# Tracksoar_v1_2.net
KiCad netlist of a schematic drawn in EAGLE
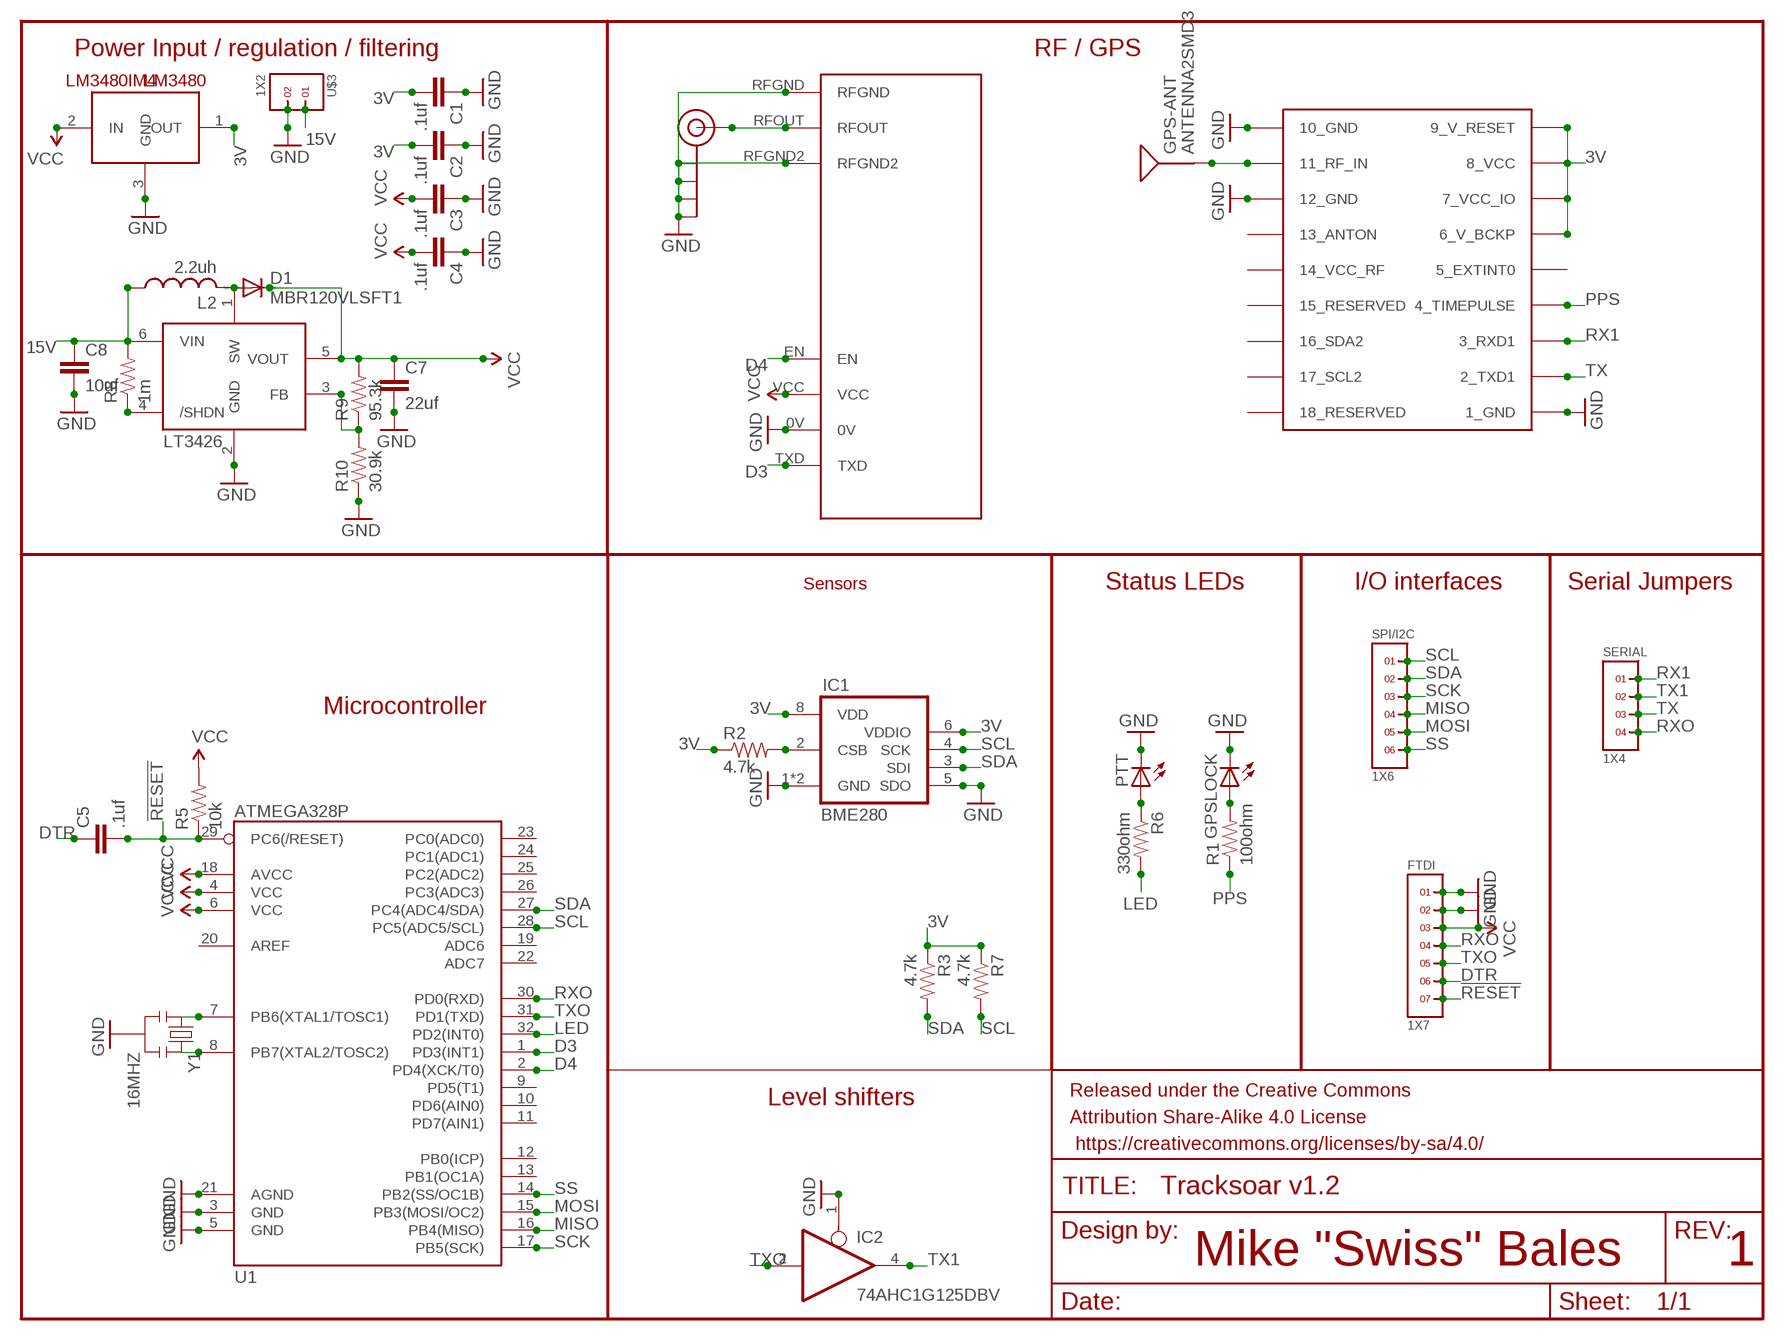
[diagram p0: schematic, sheet 1]

(export (version "E")
  (design (tool "Eeschema 10.0.6"))
  (components
    (comp (ref "C1")
      (value ".1uf")
      (footprint "eagle-import:0805")
      (libsource (lib "eagle-import") (part "CAP0805"))
    )
    (comp (ref "C2")
      (value ".1uf")
      (footprint "eagle-import:0805")
      (libsource (lib "eagle-import") (part "CAP0805"))
    )
    (comp (ref "C3")
      (value ".1uf")
      (footprint "eagle-import:0805")
      (libsource (lib "eagle-import") (part "CAP0805"))
    )
    (comp (ref "C4")
      (value ".1uf")
      (footprint "eagle-import:0805")
      (libsource (lib "eagle-import") (part "CAP0805"))
    )
    (comp (ref "C5")
      (value ".1uf")
      (footprint "eagle-import:0805")
      (libsource (lib "eagle-import") (part "CAP0805"))
    )
    (comp (ref "C7")
      (value "22uf")
      (footprint "eagle-import:0805")
      (libsource (lib "eagle-import") (part "CAP0805"))
    )
    (comp (ref "C8")
      (value "10uf")
      (footprint "eagle-import:0805")
      (libsource (lib "eagle-import") (part "CAP0805"))
    )
    (comp (ref "D1")
      (value "MBR120VLSFT1")
      (footprint "eagle-import:SOD123")
      (libsource (lib "eagle-import") (part "DIODE-SOD123"))
    )
    (comp (ref "FRAME1")
      (value "FRAME-LETTER")
      (footprint "eagle-import:CREATIVE_COMMONS")
      (libsource (lib "eagle-import") (part "FRAME-LETTER"))
    )
    (comp (ref "FTDI")
      (value "1X7")
      (footprint "eagle-import:1X7")
      (libsource (lib "eagle-import") (part "1X7"))
    )
    (comp (ref "GPS-ANT")
      (value "ANTENNA2SMD3")
      (footprint "eagle-import:ANTENNA-CHIP4")
      (libsource (lib "eagle-import") (part "ANTENNA2SMD3"))
    )
    (comp (ref "GPSLOCK")
      (value "LEDCHIP-LED0805")
      (footprint "eagle-import:CHIP-LED0805")
      (libsource (lib "eagle-import") (part "LEDCHIP-LED0805"))
    )
    (comp (ref "IC1")
      (value "BME280")
      (footprint "eagle-import:BME280")
      (libsource (lib "eagle-import") (part "BME280"))
    )
    (comp (ref "IC2")
      (value "74AHC1G125DBV")
      (footprint "eagle-import:SOT23-5")
      (libsource (lib "eagle-import") (part "741G125DBVAHC"))
    )
    (comp (ref "J$1")
      (value "SMA_EDGE")
      (footprint "eagle-import:SMA-EDGE")
      (libsource (lib "eagle-import") (part "SMA_EDGE"))
    )
    (comp (ref "L2")
      (value "2.2uh")
      (footprint "eagle-import:L1812")
      (libsource (lib "eagle-import") (part "L-USL1812"))
    )
    (comp (ref "LM3480")
      (value "LM3480IM4")
      (footprint "eagle-import:SOT23-3")
      (libsource (lib "eagle-import") (part "LM3480IM4"))
    )
    (comp (ref "LT3426")
      (value "LT3426")
      (footprint "eagle-import:SOT23-6")
      (libsource (lib "eagle-import") (part "LT3426"))
    )
    (comp (ref "PTT")
      (value "LEDCHIP-LED0805")
      (footprint "eagle-import:CHIP-LED0805")
      (libsource (lib "eagle-import") (part "LEDCHIP-LED0805"))
    )
    (comp (ref "R1")
      (value "100ohm")
      (footprint "eagle-import:0805")
      (libsource (lib "eagle-import") (part "RESISTOR0805-RES"))
    )
    (comp (ref "R2")
      (value "4.7k")
      (footprint "eagle-import:0805")
      (libsource (lib "eagle-import") (part "RESISTOR0805-RES"))
    )
    (comp (ref "R3")
      (value "4.7k")
      (footprint "eagle-import:0805")
      (libsource (lib "eagle-import") (part "RESISTOR0805-RES"))
    )
    (comp (ref "R5")
      (value "10k")
      (footprint "eagle-import:0805")
      (libsource (lib "eagle-import") (part "RESISTOR0805-RES"))
    )
    (comp (ref "R6")
      (value "330ohm")
      (footprint "eagle-import:0805")
      (libsource (lib "eagle-import") (part "RESISTOR0805-RES"))
    )
    (comp (ref "R7")
      (value "4.7k")
      (footprint "eagle-import:0805")
      (libsource (lib "eagle-import") (part "RESISTOR0805-RES"))
    )
    (comp (ref "R8")
      (value "1m")
      (footprint "eagle-import:0805")
      (libsource (lib "eagle-import") (part "RESISTOR0805-RES"))
    )
    (comp (ref "R9")
      (value "95.3k")
      (footprint "eagle-import:0805")
      (libsource (lib "eagle-import") (part "RESISTOR0805-RES"))
    )
    (comp (ref "R10")
      (value "30.9k")
      (footprint "eagle-import:0805")
      (libsource (lib "eagle-import") (part "RESISTOR0805-RES"))
    )
    (comp (ref "SERIAL")
      (value "1X4")
      (footprint "eagle-import:1X4")
      (libsource (lib "eagle-import") (part "1X4"))
    )
    (comp (ref "SPI/I2C")
      (value "1X6")
      (footprint "eagle-import:1X6")
      (libsource (lib "eagle-import") (part "1X6"))
    )
    (comp (ref "U$1")
      (value "UBLOX_MAX")
      (footprint "eagle-import:UBLOX_MAX")
      (libsource (lib "eagle-import") (part "UBLOX_MAX"))
    )
    (comp (ref "U$2")
      (value "RADIOMETRIX-HX1")
      (footprint "eagle-import:RADIOMETRIX-HX1")
      (libsource (lib "eagle-import") (part "RADIOMETRIX-HX1"))
    )
    (comp (ref "U$3")
      (value "1X2")
      (footprint "eagle-import:1X2")
      (libsource (lib "eagle-import") (part "1X2"))
    )
    (comp (ref "U1")
      (value "ATMEGA328P")
      (footprint "eagle-import:MLF32")
      (libsource (lib "eagle-import") (part "ATMEGA168MLF"))
    )
    (comp (ref "Y1")
      (value "16MHZ")
      (footprint "eagle-import:RESONATOR-SMD")
      (libsource (lib "eagle-import") (part "RESONATOR16MHZ"))
    )
  )
  (nets
    (net (code "1") (name "/3V") (class "Default")
      (node (ref "C1") (pin "2") (pinfunction "2_2") (pintype "passive"))
      (node (ref "C2") (pin "2") (pinfunction "2_2") (pintype "passive"))
      (node (ref "IC1") (pin "6") (pinfunction "VDDIO_6") (pintype "power_in"))
      (node (ref "IC1") (pin "8") (pinfunction "VDD_8") (pintype "power_in"))
      (node (ref "LM3480") (pin "1") (pinfunction "OUT_1") (pintype "bidirectional"))
      (node (ref "R2") (pin "1") (pinfunction "1_1") (pintype "passive"))
      (node (ref "R3") (pin "1") (pinfunction "1_1") (pintype "passive"))
      (node (ref "R7") (pin "1") (pinfunction "1_1") (pintype "passive"))
      (node (ref "U$1") (pin "6_V_BCKP") (pinfunction "6_V_BCKP_6_V_BCKP") (pintype "bidirectional"))
      (node (ref "U$1") (pin "7_VCC_IO") (pinfunction "7_VCC_IO_7_VCC_IO") (pintype "power_in"))
      (node (ref "U$1") (pin "8_VCC") (pinfunction "8_VCC_8_VCC") (pintype "power_in"))
      (node (ref "U$1") (pin "9_V_RESET") (pinfunction "9_V_RESET_9_V_RESET") (pintype "power_in"))
    )
    (net (code "2") (name "/15V") (class "Default")
      (node (ref "C8") (pin "1") (pinfunction "1_1") (pintype "passive"))
      (node (ref "L2") (pin "1") (pinfunction "1_1") (pintype "passive"))
      (node (ref "LT3426") (pin "6") (pinfunction "VIN_6") (pintype "input"))
      (node (ref "R8") (pin "2") (pinfunction "2_2") (pintype "passive"))
      (node (ref "U$3") (pin "1") (pinfunction "1_1") (pintype "bidirectional"))
    )
    (net (code "3") (name "/D3") (class "Default")
      (node (ref "U$2") (pin "TXD") (pinfunction "TXD_TXD") (pintype "bidirectional"))
      (node (ref "U1") (pin "1") (pinfunction "PD3(INT1)_1") (pintype "bidirectional"))
    )
    (net (code "4") (name "/D4") (class "Default")
      (node (ref "U$2") (pin "EN") (pinfunction "EN_EN") (pintype "bidirectional"))
      (node (ref "U1") (pin "2") (pinfunction "PD4(XCK/T0)_2") (pintype "bidirectional"))
    )
    (net (code "5") (name "/DTR") (class "Default")
      (node (ref "C5") (pin "1") (pinfunction "1_1") (pintype "passive"))
      (node (ref "FTDI") (pin "6") (pinfunction "6_6") (pintype "bidirectional"))
    )
    (net (code "6") (name "/LED") (class "Default")
      (node (ref "R6") (pin "2") (pinfunction "2_2") (pintype "passive"))
      (node (ref "U1") (pin "32") (pinfunction "PD2(INT0)_32") (pintype "bidirectional"))
    )
    (net (code "7") (name "/MISO") (class "Default")
      (node (ref "SPI/I2C") (pin "4") (pinfunction "4_4") (pintype "bidirectional"))
      (node (ref "U1") (pin "16") (pinfunction "PB4(MISO)_16") (pintype "bidirectional"))
    )
    (net (code "8") (name "/MOSI") (class "Default")
      (node (ref "SPI/I2C") (pin "5") (pinfunction "5_5") (pintype "bidirectional"))
      (node (ref "U1") (pin "15") (pinfunction "PB3(MOSI/OC2)_15") (pintype "bidirectional"))
    )
    (net (code "9") (name "/PPS") (class "Default")
      (node (ref "R1") (pin "1") (pinfunction "1_1") (pintype "passive"))
      (node (ref "U$1") (pin "4_TIMEPULSE") (pinfunction "4_TIMEPULSE_4_TIMEPULSE") (pintype "bidirectional"))
    )
    (net (code "10") (name "/RX1") (class "Default")
      (node (ref "SERIAL") (pin "1") (pinfunction "1_1") (pintype "bidirectional"))
      (node (ref "U$1") (pin "3_RXD1") (pinfunction "3_RXD1_3_RXD1") (pintype "bidirectional"))
    )
    (net (code "11") (name "/RXO") (class "Default")
      (node (ref "FTDI") (pin "4") (pinfunction "4_4") (pintype "bidirectional"))
      (node (ref "SERIAL") (pin "4") (pinfunction "4_4") (pintype "bidirectional"))
      (node (ref "U1") (pin "30") (pinfunction "PD0(RXD)_30") (pintype "bidirectional"))
    )
    (net (code "12") (name "/SCK") (class "Default")
      (node (ref "SPI/I2C") (pin "3") (pinfunction "3_3") (pintype "bidirectional"))
      (node (ref "U1") (pin "17") (pinfunction "PB5(SCK)_17") (pintype "bidirectional"))
    )
    (net (code "13") (name "/SCL") (class "Default")
      (node (ref "IC1") (pin "4") (pinfunction "SCK_4") (pintype "bidirectional"))
      (node (ref "R7") (pin "2") (pinfunction "2_2") (pintype "passive"))
      (node (ref "SPI/I2C") (pin "1") (pinfunction "1_1") (pintype "bidirectional"))
      (node (ref "U1") (pin "28") (pinfunction "PC5(ADC5/SCL)_28") (pintype "bidirectional"))
    )
    (net (code "14") (name "/SDA") (class "Default")
      (node (ref "IC1") (pin "3") (pinfunction "SDI_3") (pintype "bidirectional"))
      (node (ref "R3") (pin "2") (pinfunction "2_2") (pintype "passive"))
      (node (ref "SPI/I2C") (pin "2") (pinfunction "2_2") (pintype "bidirectional"))
      (node (ref "U1") (pin "27") (pinfunction "PC4(ADC4/SDA)_27") (pintype "bidirectional"))
    )
    (net (code "15") (name "/SS") (class "Default")
      (node (ref "SPI/I2C") (pin "6") (pinfunction "6_6") (pintype "bidirectional"))
      (node (ref "U1") (pin "14") (pinfunction "PB2(SS/OC1B)_14") (pintype "bidirectional"))
    )
    (net (code "16") (name "/TX") (class "Default")
      (node (ref "SERIAL") (pin "3") (pinfunction "3_3") (pintype "bidirectional"))
      (node (ref "U$1") (pin "2_TXD1") (pinfunction "2_TXD1_2_TXD1") (pintype "bidirectional"))
    )
    (net (code "17") (name "/TX1") (class "Default")
      (node (ref "IC2") (pin "4") (pinfunction "O_4") (pintype "tri_state"))
      (node (ref "SERIAL") (pin "2") (pinfunction "2_2") (pintype "bidirectional"))
    )
    (net (code "18") (name "/TXO") (class "Default")
      (node (ref "FTDI") (pin "5") (pinfunction "5_5") (pintype "bidirectional"))
      (node (ref "IC2") (pin "2") (pinfunction "I_2") (pintype "input"))
      (node (ref "U1") (pin "31") (pinfunction "PD1(TXD)_31") (pintype "bidirectional"))
    )
    (net (code "19") (name "/~{RESET}") (class "Default")
      (node (ref "C5") (pin "2") (pinfunction "2_2") (pintype "passive"))
      (node (ref "FTDI") (pin "7") (pinfunction "7_7") (pintype "bidirectional"))
      (node (ref "R5") (pin "1") (pinfunction "1_1") (pintype "passive"))
      (node (ref "U1") (pin "29") (pinfunction "PC6(/RESET)_29") (pintype "bidirectional"))
    )
    (net (code "20") (name "GND") (class "Default")
      (node (ref "C1") (pin "1") (pinfunction "1_1") (pintype "passive"))
      (node (ref "C2") (pin "1") (pinfunction "1_1") (pintype "passive"))
      (node (ref "C3") (pin "1") (pinfunction "1_1") (pintype "passive"))
      (node (ref "C4") (pin "1") (pinfunction "1_1") (pintype "passive"))
      (node (ref "C7") (pin "2") (pinfunction "2_2") (pintype "passive"))
      (node (ref "C8") (pin "2") (pinfunction "2_2") (pintype "passive"))
      (node (ref "FTDI") (pin "1") (pinfunction "1_1") (pintype "bidirectional"))
      (node (ref "FTDI") (pin "2") (pinfunction "2_2") (pintype "bidirectional"))
      (node (ref "GPSLOCK") (pin "C") (pinfunction "C_C") (pintype "passive"))
      (node (ref "IC1") (pin "1") (pinfunction "GND_1") (pintype "power_in"))
      (node (ref "IC1") (pin "5") (pinfunction "SDO_5") (pintype "input"))
      (node (ref "IC1") (pin "7") (pinfunction "GND_7") (pintype "power_in"))
      (node (ref "IC2") (pin "1") (pinfunction "OE_1") (pintype "input"))
      (node (ref "J$1") (pin "GND@0") (pinfunction "GND_GND@0") (pintype "bidirectional"))
      (node (ref "J$1") (pin "GND@1") (pinfunction "GND_GND@1") (pintype "bidirectional"))
      (node (ref "J$1") (pin "GND@2") (pinfunction "GND_GND@2") (pintype "bidirectional"))
      (node (ref "J$1") (pin "GND@3") (pinfunction "GND_GND@3") (pintype "bidirectional"))
      (node (ref "LM3480") (pin "3") (pinfunction "GND_3") (pintype "bidirectional"))
      (node (ref "LT3426") (pin "2") (pinfunction "GND_2") (pintype "power_in"))
      (node (ref "PTT") (pin "C") (pinfunction "C_C") (pintype "passive"))
      (node (ref "R10") (pin "1") (pinfunction "1_1") (pintype "passive"))
      (node (ref "U$1") (pin "10_GND") (pinfunction "10_GND_10_GND") (pintype "power_in"))
      (node (ref "U$1") (pin "12_GND") (pinfunction "12_GND_12_GND") (pintype "power_in"))
      (node (ref "U$1") (pin "1_GND") (pinfunction "1_GND_1_GND") (pintype "power_in"))
      (node (ref "U$2") (pin "0V") (pinfunction "0V_0V") (pintype "bidirectional"))
      (node (ref "U$2") (pin "RFGND") (pinfunction "RFGND_RFGND") (pintype "bidirectional"))
      (node (ref "U$2") (pin "RFGND2") (pinfunction "RFGND2_RFGND2") (pintype "bidirectional"))
      (node (ref "U$3") (pin "2") (pinfunction "2_2") (pintype "bidirectional"))
      (node (ref "U1") (pin "21") (pinfunction "AGND_21") (pintype "bidirectional"))
      (node (ref "U1") (pin "3") (pinfunction "GND_3") (pintype "bidirectional"))
      (node (ref "U1") (pin "5") (pinfunction "GND_5") (pintype "bidirectional"))
      (node (ref "Y1") (pin "2") (pinfunction "2_2") (pintype "passive"))
    )
    (net (code "21") (name "Net-(GPS-ANT-SIGNAL)") (class "Default")
      (node (ref "GPS-ANT") (pin "SIG") (pinfunction "SIGNAL_SIG") (pintype "bidirectional"))
      (node (ref "U$1") (pin "11_RF_IN") (pinfunction "11_RF_IN_11_RF_IN") (pintype "bidirectional"))
    )
    (net (code "22") (name "Net-(GPSLOCK-PadA)") (class "Default")
      (node (ref "GPSLOCK") (pin "A") (pinfunction "A_A") (pintype "passive"))
      (node (ref "R1") (pin "2") (pinfunction "2_2") (pintype "passive"))
    )
    (net (code "23") (name "Net-(IC1-CSB)") (class "Default")
      (node (ref "IC1") (pin "2") (pinfunction "CSB_2") (pintype "input"))
      (node (ref "R2") (pin "2") (pinfunction "2_2") (pintype "passive"))
    )
    (net (code "24") (name "Net-(J$1-SIGNAL)") (class "Default")
      (node (ref "J$1") (pin "SIG") (pinfunction "SIGNAL_SIG") (pintype "bidirectional"))
      (node (ref "U$2") (pin "RFOUT") (pinfunction "RFOUT_RFOUT") (pintype "bidirectional"))
    )
    (net (code "25") (name "Net-(LT3426-FB)") (class "Default")
      (node (ref "LT3426") (pin "3") (pinfunction "FB_3") (pintype "input"))
      (node (ref "R10") (pin "2") (pinfunction "2_2") (pintype "passive"))
      (node (ref "R9") (pin "1") (pinfunction "1_1") (pintype "passive"))
    )
    (net (code "26") (name "Net-(LT3426-SW)") (class "Default")
      (node (ref "D1") (pin "A") (pinfunction "A_A") (pintype "passive"))
      (node (ref "L2") (pin "2") (pinfunction "2_2") (pintype "passive"))
      (node (ref "LT3426") (pin "1") (pinfunction "SW_1") (pintype "output"))
    )
    (net (code "27") (name "Net-(LT3426-{slash}SHDN)") (class "Default")
      (node (ref "LT3426") (pin "4") (pinfunction "/SHDN_4") (pintype "input"))
      (node (ref "R8") (pin "1") (pinfunction "1_1") (pintype "passive"))
    )
    (net (code "28") (name "Net-(PTT-PadA)") (class "Default")
      (node (ref "PTT") (pin "A") (pinfunction "A_A") (pintype "passive"))
      (node (ref "R6") (pin "1") (pinfunction "1_1") (pintype "passive"))
    )
    (net (code "29") (name "Net-(U1-PB6(XTAL1{slash}TOSC1))") (class "Default")
      (node (ref "U1") (pin "7") (pinfunction "PB6(XTAL1/TOSC1)_7") (pintype "bidirectional"))
      (node (ref "Y1") (pin "1") (pinfunction "1_1") (pintype "passive"))
    )
    (net (code "30") (name "Net-(U1-PB7(XTAL2{slash}TOSC2))") (class "Default")
      (node (ref "U1") (pin "8") (pinfunction "PB7(XTAL2/TOSC2)_8") (pintype "bidirectional"))
      (node (ref "Y1") (pin "3") (pinfunction "3_3") (pintype "passive"))
    )
    (net (code "31") (name "VCC") (class "Default")
      (node (ref "C3") (pin "2") (pinfunction "2_2") (pintype "passive"))
      (node (ref "C4") (pin "2") (pinfunction "2_2") (pintype "passive"))
      (node (ref "C7") (pin "1") (pinfunction "1_1") (pintype "passive"))
      (node (ref "D1") (pin "C") (pinfunction "C_C") (pintype "passive"))
      (node (ref "FTDI") (pin "3") (pinfunction "3_3") (pintype "bidirectional"))
      (node (ref "LM3480") (pin "2") (pinfunction "IN_2") (pintype "bidirectional"))
      (node (ref "LT3426") (pin "5") (pinfunction "VOUT_5") (pintype "output"))
      (node (ref "R5") (pin "2") (pinfunction "2_2") (pintype "passive"))
      (node (ref "R9") (pin "2") (pinfunction "2_2") (pintype "passive"))
      (node (ref "U$2") (pin "VCC") (pinfunction "VCC_VCC") (pintype "bidirectional"))
      (node (ref "U1") (pin "18") (pinfunction "AVCC_18") (pintype "bidirectional"))
      (node (ref "U1") (pin "4") (pinfunction "VCC_4") (pintype "bidirectional"))
      (node (ref "U1") (pin "6") (pinfunction "VCC_6") (pintype "bidirectional"))
    )
    (net (code "32") (name "unconnected-(U$1-Pad5_EXTINT0)") (class "Default")
      (node (ref "U$1") (pin "5_EXTINT0") (pinfunction "5_EXTINT0_5_EXTINT0") (pintype "bidirectional"))
    )
    (net (code "33") (name "unconnected-(U$1-Pad13_ANTON)") (class "Default")
      (node (ref "U$1") (pin "13_ANTON") (pinfunction "13_ANTON_13_ANTON") (pintype "bidirectional"))
    )
    (net (code "34") (name "unconnected-(U$1-Pad14_VCC_RF)") (class "Default")
      (node (ref "U$1") (pin "14_VCC_RF") (pinfunction "14_VCC_RF_14_VCC_RF") (pintype "bidirectional"))
    )
    (net (code "35") (name "unconnected-(U$1-Pad15_RESERVED)") (class "Default")
      (node (ref "U$1") (pin "15_RESERVED") (pinfunction "15_RESERVED_15_RESERVED") (pintype "bidirectional"))
    )
    (net (code "36") (name "unconnected-(U$1-Pad16_SDA2)") (class "Default")
      (node (ref "U$1") (pin "16_SDA2") (pinfunction "16_SDA2_16_SDA2") (pintype "bidirectional"))
    )
    (net (code "37") (name "unconnected-(U$1-Pad17_SCL2)") (class "Default")
      (node (ref "U$1") (pin "17_SCL2") (pinfunction "17_SCL2_17_SCL2") (pintype "bidirectional"))
    )
    (net (code "38") (name "unconnected-(U$1-Pad18_RESERVED)") (class "Default")
      (node (ref "U$1") (pin "18_RESERVED") (pinfunction "18_RESERVED_18_RESERVED") (pintype "bidirectional"))
    )
    (net (code "39") (name "unconnected-(U1-ADC6-Pad19)") (class "Default")
      (node (ref "U1") (pin "19") (pinfunction "ADC6_19") (pintype "bidirectional"))
    )
    (net (code "40") (name "unconnected-(U1-ADC7-Pad22)") (class "Default")
      (node (ref "U1") (pin "22") (pinfunction "ADC7_22") (pintype "bidirectional"))
    )
    (net (code "41") (name "unconnected-(U1-AREF-Pad20)") (class "Default")
      (node (ref "U1") (pin "20") (pinfunction "AREF_20") (pintype "bidirectional"))
    )
    (net (code "42") (name "unconnected-(U1-PB0(ICP)-Pad12)") (class "Default")
      (node (ref "U1") (pin "12") (pinfunction "PB0(ICP)_12") (pintype "bidirectional"))
    )
    (net (code "43") (name "unconnected-(U1-PB1(OC1A)-Pad13)") (class "Default")
      (node (ref "U1") (pin "13") (pinfunction "PB1(OC1A)_13") (pintype "bidirectional"))
    )
    (net (code "44") (name "unconnected-(U1-PC0(ADC0)-Pad23)") (class "Default")
      (node (ref "U1") (pin "23") (pinfunction "PC0(ADC0)_23") (pintype "bidirectional"))
    )
    (net (code "45") (name "unconnected-(U1-PC1(ADC1)-Pad24)") (class "Default")
      (node (ref "U1") (pin "24") (pinfunction "PC1(ADC1)_24") (pintype "bidirectional"))
    )
    (net (code "46") (name "unconnected-(U1-PC2(ADC2)-Pad25)") (class "Default")
      (node (ref "U1") (pin "25") (pinfunction "PC2(ADC2)_25") (pintype "bidirectional"))
    )
    (net (code "47") (name "unconnected-(U1-PC3(ADC3)-Pad26)") (class "Default")
      (node (ref "U1") (pin "26") (pinfunction "PC3(ADC3)_26") (pintype "bidirectional"))
    )
    (net (code "48") (name "unconnected-(U1-PD5(T1)-Pad9)") (class "Default")
      (node (ref "U1") (pin "9") (pinfunction "PD5(T1)_9") (pintype "bidirectional"))
    )
    (net (code "49") (name "unconnected-(U1-PD6(AIN0)-Pad10)") (class "Default")
      (node (ref "U1") (pin "10") (pinfunction "PD6(AIN0)_10") (pintype "bidirectional"))
    )
    (net (code "50") (name "unconnected-(U1-PD7(AIN1)-Pad11)") (class "Default")
      (node (ref "U1") (pin "11") (pinfunction "PD7(AIN1)_11") (pintype "bidirectional"))
    )
  )
)
